# tempcontroller_schematic.net
KiCad netlist of a schematic drawn in EAGLE
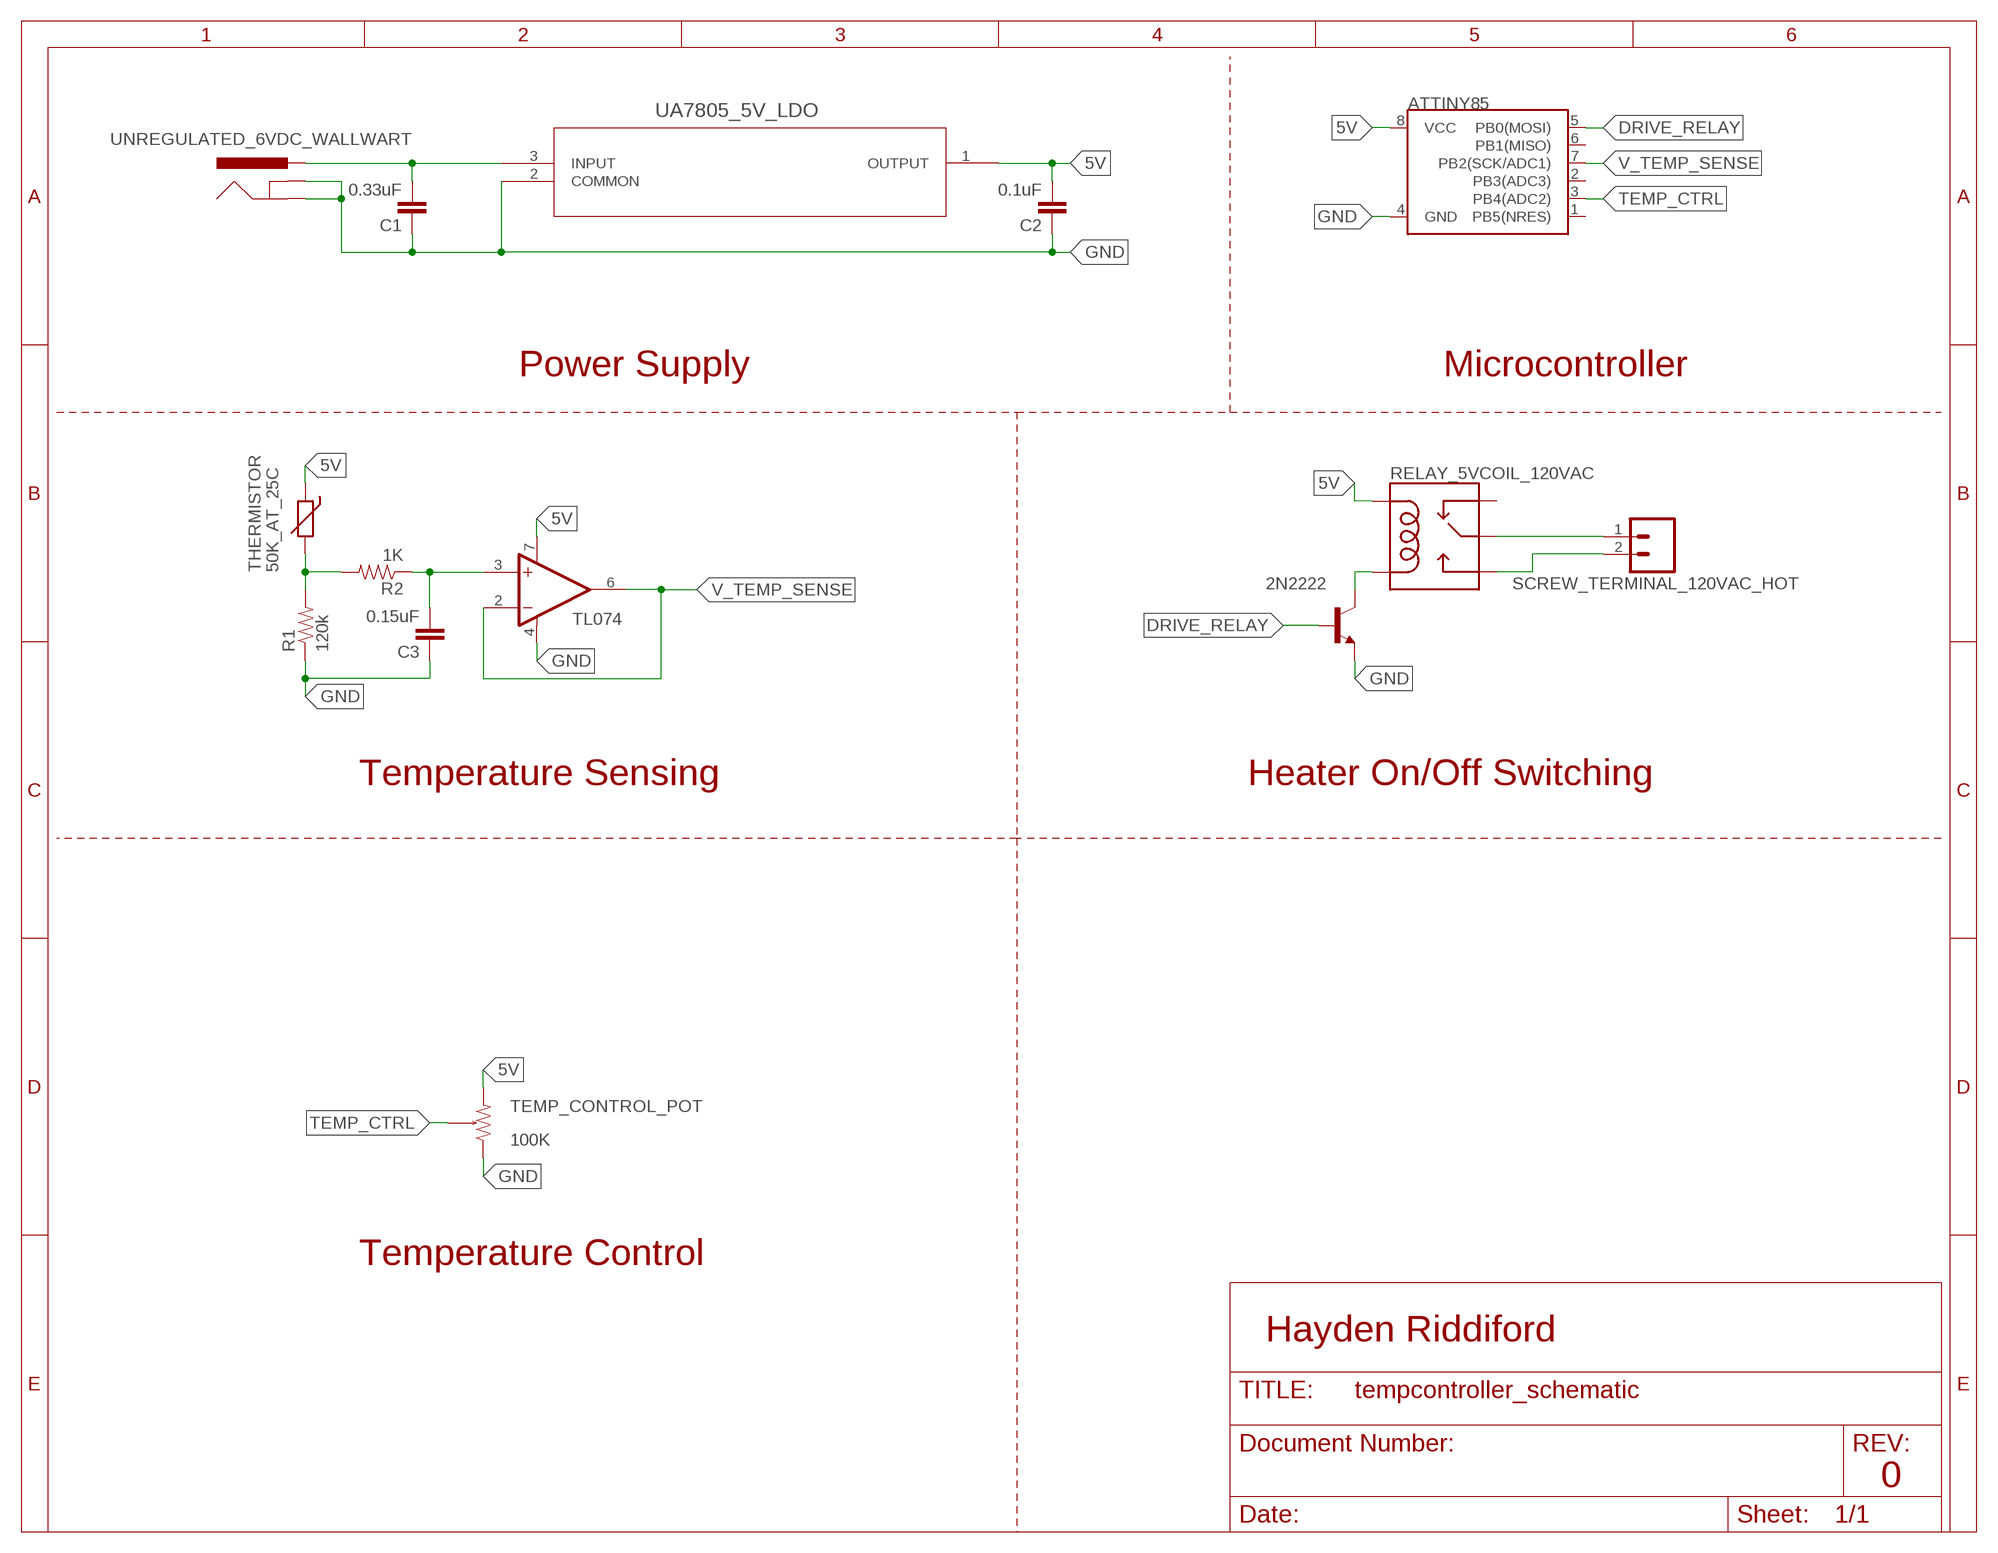
[diagram p0: schematic, sheet 1]

(export (version "E")
  (design (tool "Eeschema 10.0.6"))
  (components
    (comp (ref "ATTINY85")
      (value "TINY85-20-DIP")
      (footprint "eagle-import:DIP08")
      (libsource (lib "eagle-import") (part "ATTINY45TINY85-20-DIP"))
    )
    (comp (ref "C1")
      (value "0.33uF")
      (footprint "eagle-import:AXIAL-5MM")
      (libsource (lib "eagle-import") (part "CAP_"))
    )
    (comp (ref "C2")
      (value "0.1uF")
      (footprint "eagle-import:AXIAL-5MM")
      (libsource (lib "eagle-import") (part "CAP_"))
    )
    (comp (ref "C3")
      (value "0.15uF")
      (footprint "eagle-import:AXIAL-5MM")
      (libsource (lib "eagle-import") (part "CAP_"))
    )
    (comp (ref "R1")
      (value "120k")
      (footprint "eagle-import:AXIAL-0.3")
      (libsource (lib "eagle-import") (part "RESISTORAXIAL-0.3"))
    )
    (comp (ref "R2")
      (value "1K")
      (footprint "eagle-import:AXIAL-0.3")
      (libsource (lib "eagle-import") (part "RESISTORAXIAL-0.3"))
    )
    (comp (ref "RELAY_5VCOIL_120VAC")
      (value "RELAYPTH")
      (footprint "eagle-import:RELAY-G5Q")
      (libsource (lib "eagle-import") (part "RELAYPTH"))
    )
    (comp (ref "SCREW_TERMINAL_120VAC_HOT")
      (value "M02POLAR")
      (footprint "eagle-import:MOLEX-1X2")
      (libsource (lib "eagle-import") (part "M02POLAR"))
    )
    (comp (ref "T1")
      (value "2N2222")
      (footprint "eagle-import:TO92-EBC-OVAL")
      (libsource (lib "eagle-import") (part "2N2222"))
    )
    (comp (ref "TEMP_CONTROL_POT")
      (value "100K")
      (footprint "eagle-import:0603-ARV")
      (libsource (lib "eagle-import") (part "POTENTIOMETER"))
    )
    (comp (ref "THERMISTOR")
      (value "50K_AT_25C")
      (footprint "eagle-import:R-5")
      (libsource (lib "eagle-import") (part "THERMISTOR_R-5"))
    )
    (comp (ref "TL074")
      (value "MAX430PA")
      (footprint "eagle-import:DIL08")
      (libsource (lib "eagle-import") (part "MAX430PA"))
    )
    (comp (ref "UA7805_5V_LDO")
      (value "UA7805_KCS_3")
      (footprint "eagle-import:KCS3")
      (fields
        (field (name "GENERIC_PART_NUMBER") "UA7805")
        (field (name "MANUFACTURER") "Texas Instruments")
        (field (name "MANUFACTURER_PART_NUMBER") "ua7805_kcs_3")
      )
      (libsource (lib "eagle-import") (part "UA7805_KCS_3"))
    )
    (comp (ref "UNREGULATED_6VDC_WALLWART")
      (value "POWER_JACKPTH")
      (footprint "eagle-import:POWER_JACK_PTH")
      (libsource (lib "eagle-import") (part "POWER_JACKPTH"))
    )
  )
  (nets
    (net (code "1") (name "5V") (class "Default")
      (node (ref "ATTINY85") (pin "8") (pinfunction "VCC_8") (pintype "bidirectional"))
      (node (ref "C2") (pin "P$2") (pinfunction "2_P$2") (pintype "passive"))
      (node (ref "RELAY_5VCOIL_120VAC") (pin "5") (pinfunction "COIL1_5") (pintype "bidirectional"))
      (node (ref "TEMP_CONTROL_POT") (pin "2") (pinfunction "2_2") (pintype "passive"))
      (node (ref "THERMISTOR") (pin "1") (pinfunction "1_1") (pintype "passive"))
      (node (ref "TL074") (pin "7") (pinfunction "V+_7") (pintype "power_in"))
      (node (ref "UA7805_5V_LDO") (pin "1") (pinfunction "OUTPUT_1") (pintype "output"))
    )
    (net (code "2") (name "DRIVE_RELAY") (class "Default")
      (node (ref "ATTINY85") (pin "5") (pinfunction "PB0(MOSI)_5") (pintype "bidirectional"))
      (node (ref "T1") (pin "B") (pinfunction "B_B") (pintype "passive"))
    )
    (net (code "3") (name "GND") (class "Default")
      (node (ref "ATTINY85") (pin "4") (pinfunction "GND_4") (pintype "bidirectional"))
      (node (ref "C1") (pin "P$1") (pinfunction "1_P$1") (pintype "passive"))
      (node (ref "C2") (pin "P$1") (pinfunction "1_P$1") (pintype "passive"))
      (node (ref "C3") (pin "P$1") (pinfunction "1_P$1") (pintype "passive"))
      (node (ref "R1") (pin "P$1") (pinfunction "1_P$1") (pintype "passive"))
      (node (ref "T1") (pin "E") (pinfunction "E_E") (pintype "passive"))
      (node (ref "TEMP_CONTROL_POT") (pin "1") (pinfunction "1_1") (pintype "passive"))
      (node (ref "TL074") (pin "4") (pinfunction "V-_4") (pintype "power_in"))
      (node (ref "UA7805_5V_LDO") (pin "2") (pinfunction "COMMON_2") (pintype "passive"))
      (node (ref "UNREGULATED_6VDC_WALLWART") (pin "GND") (pinfunction "GND_GND") (pintype "bidirectional"))
      (node (ref "UNREGULATED_6VDC_WALLWART") (pin "GNDBREAK") (pinfunction "GNDBREAK_GNDBREAK") (pintype "bidirectional"))
    )
    (net (code "4") (name "Net-(C1-2)") (class "Default")
      (node (ref "C1") (pin "P$2") (pinfunction "2_P$2") (pintype "passive"))
      (node (ref "UA7805_5V_LDO") (pin "3") (pinfunction "INPUT_3") (pintype "input"))
      (node (ref "UNREGULATED_6VDC_WALLWART") (pin "PWR") (pinfunction "PWR_PWR") (pintype "bidirectional"))
    )
    (net (code "5") (name "Net-(C3-2)") (class "Default")
      (node (ref "C3") (pin "P$2") (pinfunction "2_P$2") (pintype "passive"))
      (node (ref "R2") (pin "P$1") (pinfunction "1_P$1") (pintype "passive"))
      (node (ref "TL074") (pin "3") (pinfunction "+IN_3") (pintype "input"))
    )
    (net (code "6") (name "Net-(R1-2)") (class "Default")
      (node (ref "R1") (pin "P$2") (pinfunction "2_P$2") (pintype "passive"))
      (node (ref "R2") (pin "P$2") (pinfunction "2_P$2") (pintype "passive"))
      (node (ref "THERMISTOR") (pin "2") (pinfunction "2_2") (pintype "passive"))
    )
    (net (code "7") (name "Net-(RELAY_5VCOIL_120VAC-COIL2)") (class "Default")
      (node (ref "RELAY_5VCOIL_120VAC") (pin "1") (pinfunction "COIL2_1") (pintype "bidirectional"))
      (node (ref "T1") (pin "C") (pinfunction "C_C") (pintype "passive"))
    )
    (net (code "8") (name "Net-(RELAY_5VCOIL_120VAC-MAIN)") (class "Default")
      (node (ref "RELAY_5VCOIL_120VAC") (pin "2") (pinfunction "MAIN_2") (pintype "bidirectional"))
      (node (ref "SCREW_TERMINAL_120VAC_HOT") (pin "1") (pinfunction "1_1") (pintype "passive"))
    )
    (net (code "9") (name "Net-(RELAY_5VCOIL_120VAC-NO)") (class "Default")
      (node (ref "RELAY_5VCOIL_120VAC") (pin "3") (pinfunction "NO_3") (pintype "bidirectional"))
      (node (ref "SCREW_TERMINAL_120VAC_HOT") (pin "2") (pinfunction "2_2") (pintype "passive"))
    )
    (net (code "10") (name "TEMP_CTRL") (class "Default")
      (node (ref "ATTINY85") (pin "3") (pinfunction "PB4(ADC2)_3") (pintype "bidirectional"))
      (node (ref "TEMP_CONTROL_POT") (pin "3") (pinfunction "P$1_3") (pintype "bidirectional"))
      (node (ref "TEMP_CONTROL_POT") (pin "4") (pinfunction "P$1_4") (pintype "bidirectional"))
      (node (ref "TEMP_CONTROL_POT") (pin "5") (pinfunction "P$1_5") (pintype "bidirectional"))
      (node (ref "TEMP_CONTROL_POT") (pin "6") (pinfunction "P$1_6") (pintype "bidirectional"))
      (node (ref "TEMP_CONTROL_POT") (pin "7") (pinfunction "P$1_7") (pintype "bidirectional"))
      (node (ref "TEMP_CONTROL_POT") (pin "8") (pinfunction "P$1_8") (pintype "bidirectional"))
    )
    (net (code "11") (name "V_TEMP_SENSE") (class "Default")
      (node (ref "ATTINY85") (pin "7") (pinfunction "PB2(SCK/ADC1)_7") (pintype "bidirectional"))
      (node (ref "TL074") (pin "2") (pinfunction "-IN_2") (pintype "input"))
      (node (ref "TL074") (pin "6") (pinfunction "OUT_6") (pintype "output"))
    )
    (net (code "12") (name "unconnected-(ATTINY85-PB1(MISO)-Pad6)") (class "Default")
      (node (ref "ATTINY85") (pin "6") (pinfunction "PB1(MISO)_6") (pintype "bidirectional"))
    )
    (net (code "13") (name "unconnected-(ATTINY85-PB3(ADC3)-Pad2)") (class "Default")
      (node (ref "ATTINY85") (pin "2") (pinfunction "PB3(ADC3)_2") (pintype "bidirectional"))
    )
    (net (code "14") (name "unconnected-(ATTINY85-PB5(NRES)-Pad1)") (class "Default")
      (node (ref "ATTINY85") (pin "1") (pinfunction "PB5(NRES)_1") (pintype "bidirectional"))
    )
    (net (code "15") (name "unconnected-(RELAY_5VCOIL_120VAC-NC-Pad4)") (class "Default")
      (node (ref "RELAY_5VCOIL_120VAC") (pin "4") (pinfunction "NC_4") (pintype "bidirectional"))
    )
  )
)
